# MCU.net
KiCad netlist of a schematic drawn in Altium Designer
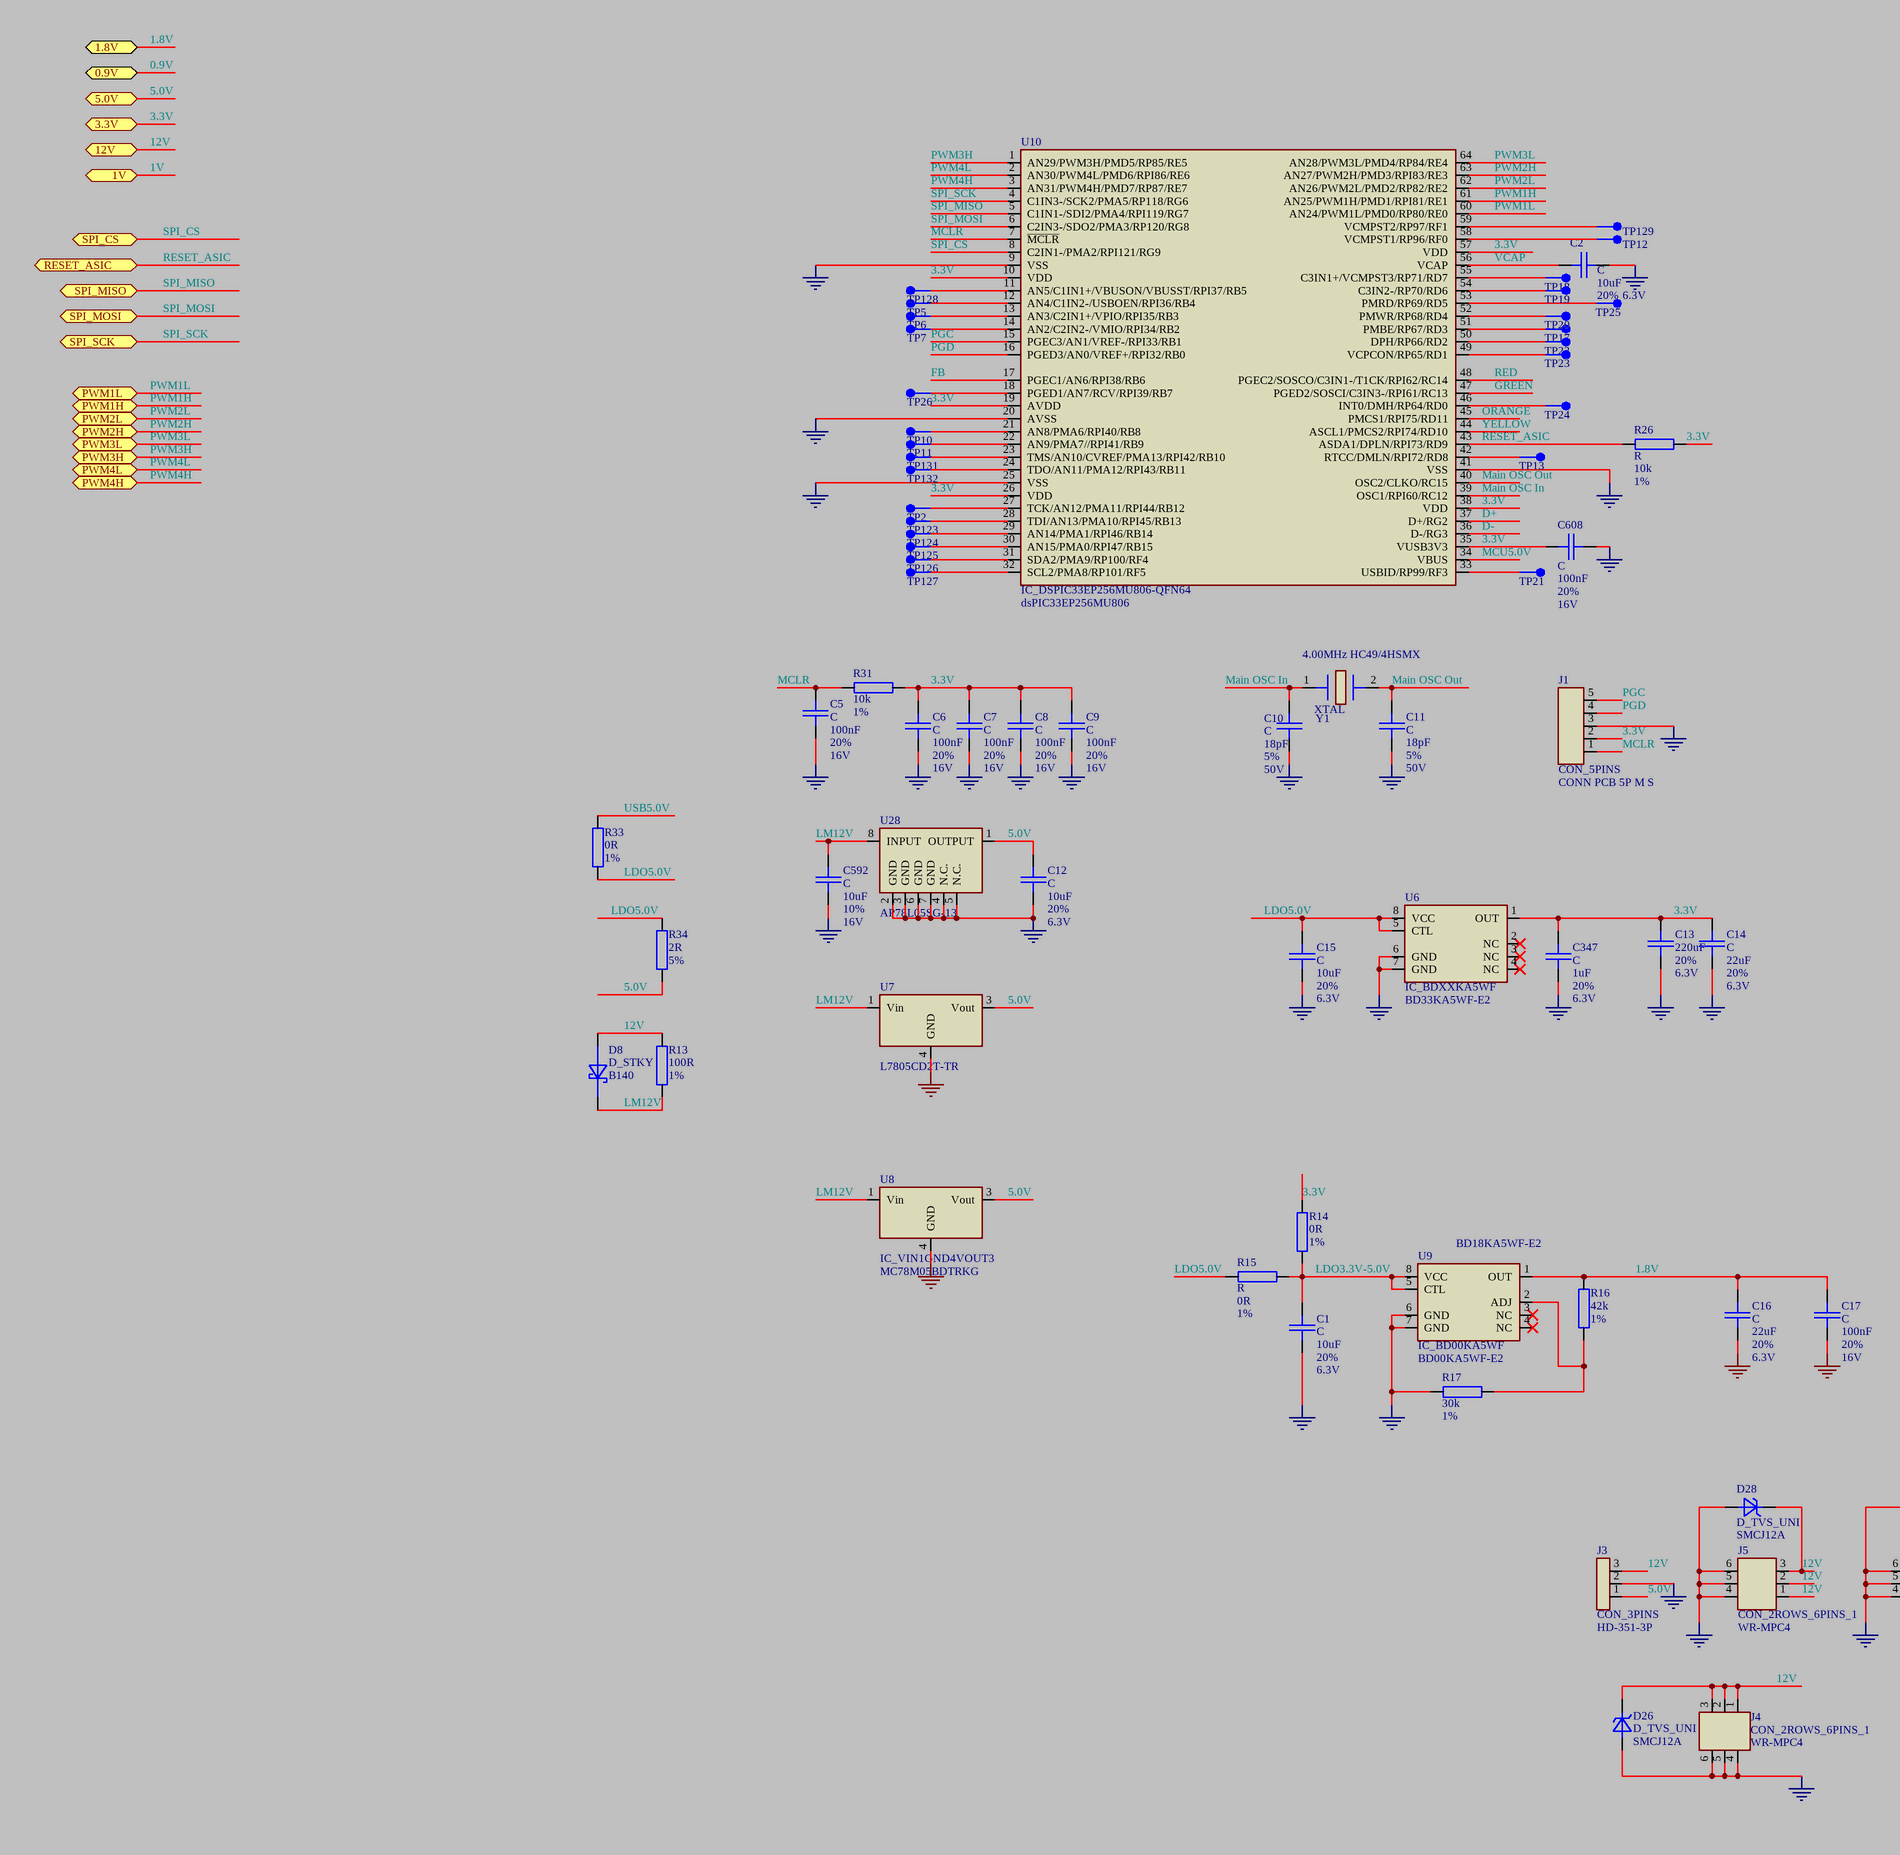
[diagram p0: MCU.SchDoc, left]
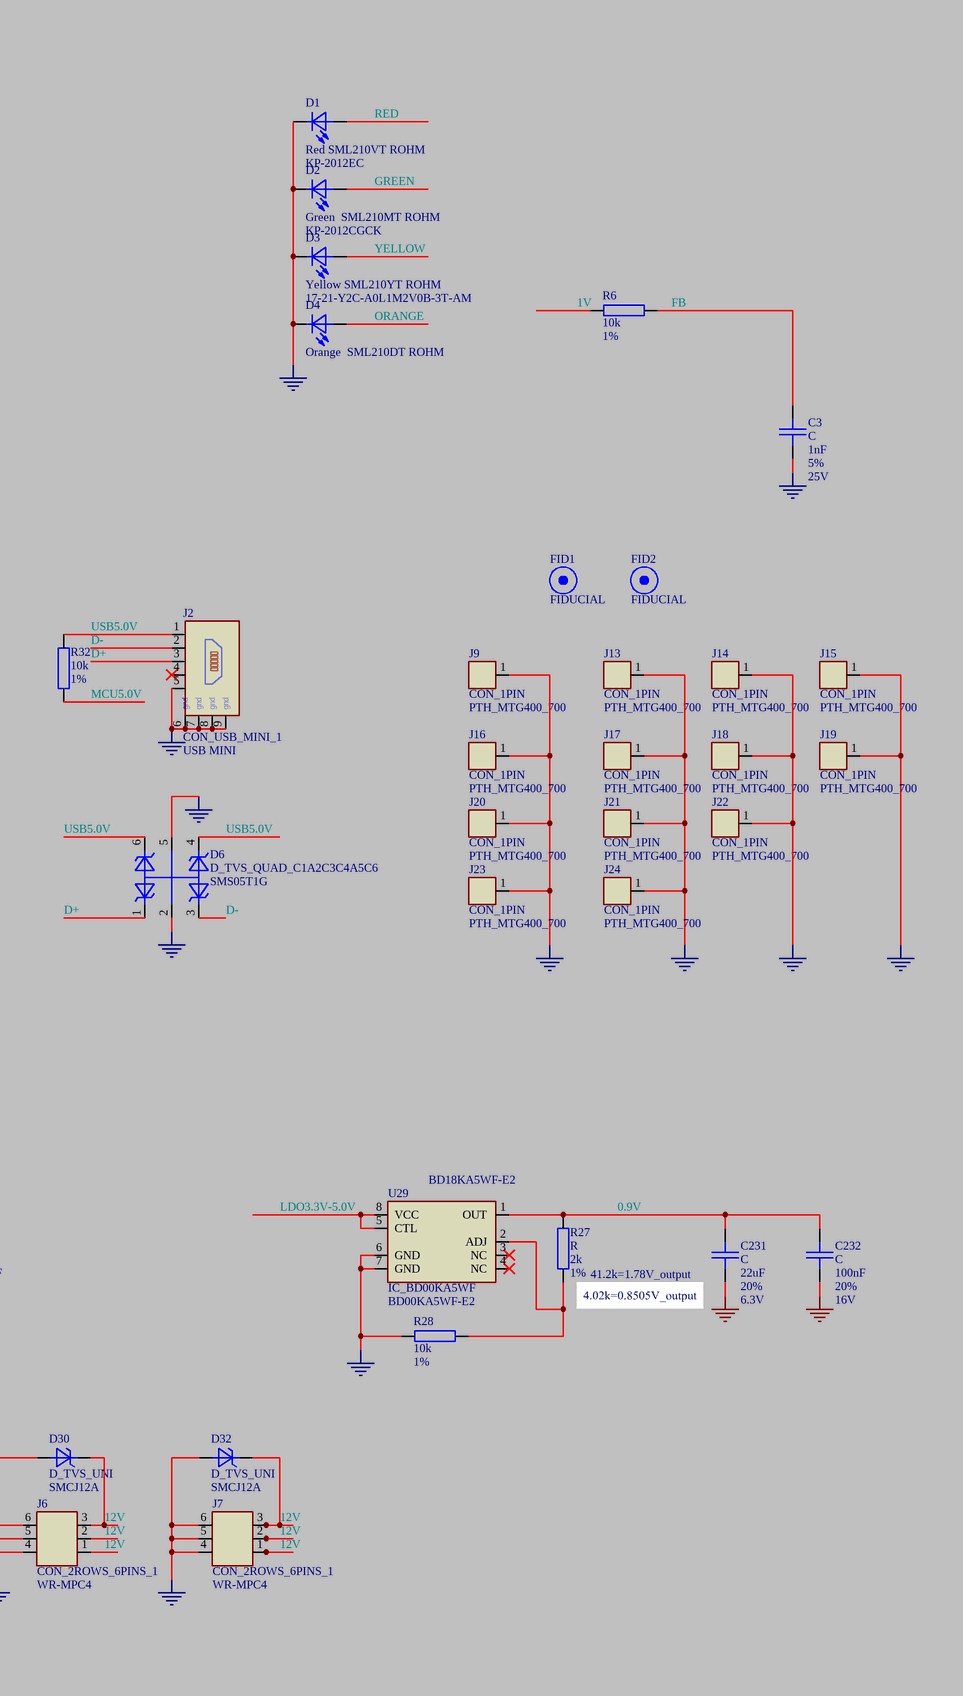
[diagram p1: MCU.SchDoc, right]

(export (version "E")
  (design (tool "Eeschema 10.0.6"))
  (components
    (comp (ref "C1")
      (value "C")
      (footprint "SMD_0603_CAPC1608X95N")
      (fields
        (field (name "DB_PART_NUMBER") "CAP000043646")
        (field (name "DB_VALUE") "10uF")
        (field (name "DB_TOLERANCE") "20%")
        (field (name "DB_VOLTAGE") "6.3V")
        (field (name "DB_MANUFACTURER_PART") "KEMET    C0603C106M9PAC")
        (field (name "DB_APPROVED_BY") "ISHIDDEN=T")
      )
      (libsource (lib "Database_Libs1") (part "C"))
    )
    (comp (ref "C2")
      (value "C")
      (footprint "SMD_0603_CAPC1608X95N")
      (fields
        (field (name "DB_PART_NUMBER") "CAP000043646")
        (field (name "DB_VALUE") "10uF")
        (field (name "DB_TOLERANCE") "20%")
        (field (name "DB_VOLTAGE") "6.3V")
        (field (name "DB_MANUFACTURER_PART") "KEMET    C0603C106M9PAC")
        (field (name "DB_APPROVED_BY") "ISHIDDEN=T")
      )
      (libsource (lib "Database_Libs1") (part "C"))
    )
    (comp (ref "C3")
      (value "C")
      (footprint "SMD_0603_CAPC1608X95N")
      (fields
        (field (name "DB_PART_NUMBER") "CAP000024113")
        (field (name "DB_VALUE") "1nF")
        (field (name "DB_TOLERANCE") "5%")
        (field (name "DB_VOLTAGE") "25V")
        (field (name "DB_MANUFACTURER_PART") "KEMET    C0603C102J3RAC")
        (field (name "DB_APPROVED_BY") "ISHIDDEN=T")
      )
      (libsource (lib "Database_Libs1") (part "C"))
    )
    (comp (ref "C5")
      (value "C")
      (footprint "SMD_0603_CAPC1608X95N")
      (fields
        (field (name "DB_PART_NUMBER") "CAP000027236")
        (field (name "DB_VALUE") "100nF")
        (field (name "DB_TOLERANCE") "20%")
        (field (name "DB_VOLTAGE") "16V")
        (field (name "DB_MANUFACTURER_PART") "KEMET    C0603C104M4RAC")
        (field (name "DB_APPROVED_BY") "ISHIDDEN=T")
      )
      (libsource (lib "Database_Libs1") (part "C"))
    )
    (comp (ref "C6")
      (value "C")
      (footprint "SMD_0603_CAPC1608X95N")
      (fields
        (field (name "DB_PART_NUMBER") "CAP000027236")
        (field (name "DB_VALUE") "100nF")
        (field (name "DB_TOLERANCE") "20%")
        (field (name "DB_VOLTAGE") "16V")
        (field (name "DB_MANUFACTURER_PART") "KEMET    C0603C104M4RAC")
        (field (name "DB_APPROVED_BY") "ISHIDDEN=T")
      )
      (libsource (lib "Database_Libs1") (part "C"))
    )
    (comp (ref "C7")
      (value "C")
      (footprint "SMD_0603_CAPC1608X95N")
      (fields
        (field (name "DB_PART_NUMBER") "CAP000027236")
        (field (name "DB_VALUE") "100nF")
        (field (name "DB_TOLERANCE") "20%")
        (field (name "DB_VOLTAGE") "16V")
        (field (name "DB_MANUFACTURER_PART") "KEMET    C0603C104M4RAC")
        (field (name "DB_APPROVED_BY") "ISHIDDEN=T")
      )
      (libsource (lib "Database_Libs1") (part "C"))
    )
    (comp (ref "C8")
      (value "C")
      (footprint "SMD_0603_CAPC1608X95N")
      (fields
        (field (name "DB_PART_NUMBER") "CAP000027236")
        (field (name "DB_VALUE") "100nF")
        (field (name "DB_TOLERANCE") "20%")
        (field (name "DB_VOLTAGE") "16V")
        (field (name "DB_MANUFACTURER_PART") "KEMET    C0603C104M4RAC")
        (field (name "DB_APPROVED_BY") "ISHIDDEN=T")
      )
      (libsource (lib "Database_Libs1") (part "C"))
    )
    (comp (ref "C9")
      (value "C")
      (footprint "SMD_0603_CAPC1608X95N")
      (fields
        (field (name "DB_PART_NUMBER") "CAP000027236")
        (field (name "DB_VALUE") "100nF")
        (field (name "DB_TOLERANCE") "20%")
        (field (name "DB_VOLTAGE") "16V")
        (field (name "DB_MANUFACTURER_PART") "KEMET    C0603C104M4RAC")
        (field (name "DB_APPROVED_BY") "ISHIDDEN=T")
      )
      (libsource (lib "Database_Libs1") (part "C"))
    )
    (comp (ref "C10")
      (value "C")
      (footprint "SMD_0603_CAPC1608X95N")
      (fields
        (field (name "DB_PART_NUMBER") "CAP000031922")
        (field (name "DB_VALUE") "18pF")
        (field (name "DB_TOLERANCE") "5%")
        (field (name "DB_VOLTAGE") "50V")
        (field (name "DB_MANUFACTURER_PART") "KEMET    C0603C180J5GAC")
        (field (name "DB_APPROVED_BY") "ISHIDDEN=T")
      )
      (libsource (lib "Database_Libs1") (part "C"))
    )
    (comp (ref "C11")
      (value "C")
      (footprint "SMD_0603_CAPC1608X95N")
      (fields
        (field (name "DB_PART_NUMBER") "CAP000031922")
        (field (name "DB_VALUE") "18pF")
        (field (name "DB_TOLERANCE") "5%")
        (field (name "DB_VOLTAGE") "50V")
        (field (name "DB_MANUFACTURER_PART") "KEMET    C0603C180J5GAC")
        (field (name "DB_APPROVED_BY") "ISHIDDEN=T")
      )
      (libsource (lib "Database_Libs1") (part "C"))
    )
    (comp (ref "C12")
      (value "C")
      (footprint "SMD_0603_CAPC1608X95N")
      (fields
        (field (name "DB_PART_NUMBER") "CAP000043646")
        (field (name "DB_VALUE") "10uF")
        (field (name "DB_TOLERANCE") "20%")
        (field (name "DB_VOLTAGE") "6.3V")
        (field (name "DB_MANUFACTURER_PART") "KEMET    C0603C106M9PAC")
        (field (name "DB_APPROVED_BY") "ISHIDDEN=T")
      )
      (libsource (lib "Database_Libs1") (part "C"))
    )
    (comp (ref "C13")
      (value "C")
      (footprint "SMD_1210_CAPC3225X279N")
      (fields
        (field (name "DB_PART_NUMBER") "CAP000047355")
        (field (name "DB_VALUE") "220uF")
        (field (name "DB_TOLERANCE") "20%")
        (field (name "DB_VOLTAGE") "6.3V")
        (field (name "DB_MANUFACTURER_PART") "SAMSUNG    CL32A227MQVNNNE")
        (field (name "DB_APPROVED_BY") "VSN")
      )
      (libsource (lib "Database_Libs1") (part "C"))
    )
    (comp (ref "C14")
      (value "C")
      (footprint "SMD_0805_CAPC2012X145N")
      (fields
        (field (name "DB_PART_NUMBER") "CAP000043686")
        (field (name "DB_VALUE") "22uF")
        (field (name "DB_TOLERANCE") "20%")
        (field (name "DB_VOLTAGE") "6.3V")
        (field (name "DB_MANUFACTURER_PART") "KEMET    C0805C226M9PAC")
        (field (name "DB_APPROVED_BY") "ISHIDDEN=T")
      )
      (libsource (lib "Database_Libs1") (part "C"))
    )
    (comp (ref "C15")
      (value "C")
      (footprint "SMD_0603_CAPC1608X95N")
      (fields
        (field (name "DB_PART_NUMBER") "CAP000043646")
        (field (name "DB_VALUE") "10uF")
        (field (name "DB_TOLERANCE") "20%")
        (field (name "DB_VOLTAGE") "6.3V")
        (field (name "DB_MANUFACTURER_PART") "KEMET    C0603C106M9PAC")
        (field (name "DB_APPROVED_BY") "ISHIDDEN=T")
      )
      (libsource (lib "Database_Libs1") (part "C"))
    )
    (comp (ref "C16")
      (value "C")
      (footprint "SMD_0805_CAPC2012X145N")
      (fields
        (field (name "DB_PART_NUMBER") "CAP000043686")
        (field (name "DB_VALUE") "22uF")
        (field (name "DB_TOLERANCE") "20%")
        (field (name "DB_VOLTAGE") "6.3V")
        (field (name "DB_MANUFACTURER_PART") "KEMET    C0805C226M9PAC")
        (field (name "DB_APPROVED_BY") "ISHIDDEN=T")
      )
      (libsource (lib "Database_Libs1") (part "C"))
    )
    (comp (ref "C17")
      (value "C")
      (footprint "SMD_0603_CAPC1608X95N")
      (fields
        (field (name "DB_PART_NUMBER") "CAP000027236")
        (field (name "DB_VALUE") "100nF")
        (field (name "DB_TOLERANCE") "20%")
        (field (name "DB_VOLTAGE") "16V")
        (field (name "DB_MANUFACTURER_PART") "KEMET    C0603C104M4RAC")
        (field (name "DB_APPROVED_BY") "ISHIDDEN=T")
      )
      (libsource (lib "Database_Libs1") (part "C"))
    )
    (comp (ref "C231")
      (value "C")
      (footprint "SMD_0805_CAPC2012X145N")
      (fields
        (field (name "DB_PART_NUMBER") "CAP000043686")
        (field (name "DB_VALUE") "22uF")
        (field (name "DB_TOLERANCE") "20%")
        (field (name "DB_VOLTAGE") "6.3V")
        (field (name "DB_MANUFACTURER_PART") "KEMET    C0805C226M9PAC")
        (field (name "DB_APPROVED_BY") "ISHIDDEN=T")
      )
      (libsource (lib "Database_Libs1") (part "C"))
    )
    (comp (ref "C232")
      (value "C")
      (footprint "SMD_0603_CAPC1608X95N")
      (fields
        (field (name "DB_PART_NUMBER") "CAP000027236")
        (field (name "DB_VALUE") "100nF")
        (field (name "DB_TOLERANCE") "20%")
        (field (name "DB_VOLTAGE") "16V")
        (field (name "DB_MANUFACTURER_PART") "KEMET    C0603C104M4RAC")
        (field (name "DB_APPROVED_BY") "ISHIDDEN=T")
      )
      (libsource (lib "Database_Libs1") (part "C"))
    )
    (comp (ref "C347")
      (value "C")
      (footprint "SMD_0603_CAPC1608X95N")
      (fields
        (field (name "DB_PART_NUMBER") "CAP000043344")
        (field (name "DB_VALUE") "1uF")
        (field (name "DB_TOLERANCE") "20%")
        (field (name "DB_VOLTAGE") "6.3V")
        (field (name "DB_MANUFACTURER_PART") "KEMET    C0603C105M9PAC")
        (field (name "DB_APPROVED_BY") "ISHIDDEN=T")
      )
      (libsource (lib "Database_Libs1") (part "C"))
    )
    (comp (ref "C592")
      (value "C")
      (footprint "SMD_0805_CAPC2012X145N")
      (fields
        (field (name "DB_PART_NUMBER") "CAP000043636")
        (field (name "DB_VALUE") "10uF")
        (field (name "DB_TOLERANCE") "10%")
        (field (name "DB_VOLTAGE") "16V")
        (field (name "DB_MANUFACTURER_PART") "KEMET    C0805C106K4PAC")
        (field (name "DB_APPROVED_BY") "ISHIDDEN=T")
      )
      (libsource (lib "Database_Libs1") (part "C"))
    )
    (comp (ref "C608")
      (value "C")
      (footprint "SMD_0603_CAPC1608X95N")
      (fields
        (field (name "DB_PART_NUMBER") "CAP000027236")
        (field (name "DB_VALUE") "100nF")
        (field (name "DB_TOLERANCE") "20%")
        (field (name "DB_VOLTAGE") "16V")
        (field (name "DB_MANUFACTURER_PART") "KEMET    C0603C104M4RAC")
        (field (name "DB_APPROVED_BY") "ISHIDDEN=T")
      )
      (libsource (lib "Database_Libs1") (part "C"))
    )
    (comp (ref "D1")
      (value "Red SML210VT ROHM")
      (footprint "SMD_0805_LED2012X100N")
      (fields
        (field (name "DB_PART_NUMBER") "OPT000000095")
        (field (name "DB_MANUFACTURER_PART") "KINGBRIGHT       KP-2012EC")
        (field (name "DB_VALUE") "KP-2012EC")
        (field (name "DB_APPROVED_BY") "VSN")
      )
      (libsource (lib "Database_Libs1") (part "LED"))
    )
    (comp (ref "D2")
      (value "Green  SML210MT ROHM")
      (footprint "SMD_0805_LED2012X100N")
      (fields
        (field (name "DB_PART_NUMBER") "OPT000000096")
        (field (name "DB_MANUFACTURER_PART") "KINGBRIGHT       KP-2012CGCK")
        (field (name "DB_VALUE") "KP-2012CGCK")
        (field (name "DB_APPROVED_BY") "VSN")
      )
      (libsource (lib "Database_Libs1") (part "LED"))
    )
    (comp (ref "D3")
      (value "Yellow SML210YT ROHM")
      (footprint "SMD_0805_LED2012X100N")
      (fields
        (field (name "DB_PART_NUMBER") "OPT000000092")
        (field (name "DB_MANUFACTURER_PART") "EVERLIGHT       17-21-Y2C-A0L1M2V0B-3T-AM")
        (field (name "DB_VALUE") "17-21-Y2C-A0L1M2V0B-3T-AM")
        (field (name "DB_APPROVED_BY") "VSN")
      )
      (libsource (lib "Database_Libs1") (part "LED"))
    )
    (comp (ref "D4")
      (value "Orange  SML210DT ROHM")
      (footprint "SMD_0805_LED2012X100N")
      (fields
        (field (name "DB_PART_NUMBER") "OPT000000096")
        (field (name "DB_MANUFACTURER_PART") "KINGBRIGHT       KP-2012CGCK")
        (field (name "DB_APPROVED_BY") "VSN")
      )
      (libsource (lib "altium-import") (part "root_0_LED_Orange_"))
    )
    (comp (ref "D6")
      (value "D_TVS_QUAD_C1A2C3C4A5C6")
      (footprint "SMD_SOT457_SOT95P275X110-6N")
      (fields
        (field (name "DB_PART_NUMBER") "DDE000002846")
        (field (name "DB_VALUE") "SMS05T1G")
        (field (name "DB_MANUFACTURER_PART") "ON SEMICONDUCTOR        SMS05T1G")
        (field (name "DB_APPROVED_BY") "VSN")
      )
      (libsource (lib "Database_Libs1") (part "D_TVS_QUAD_C1A2C3C4A5C6"))
    )
    (comp (ref "D8")
      (value "D_STKY")
      (footprint "SMD_DO214AC_SMA")
      (fields
        (field (name "DB_PART_NUMBER") "DDE000000580")
        (field (name "DB_VALUE") "B140")
        (field (name "DB_MANUFACTURER_PART") "Diodes        B140")
        (field (name "DB_APPROVED_BY") "ISHIDDEN=T")
      )
      (libsource (lib "Database_Libs1") (part "D_STKY"))
    )
    (comp (ref "D26")
      (value "D_TVS_UNI")
      (footprint "SMD_DO214AC_SMC")
      (fields
        (field (name "DB_PART_NUMBER") "DDE000001725")
        (field (name "DB_VALUE") "SMCJ12A")
        (field (name "DB_MANUFACTURER_PART") "Diodes        SMCJ12A")
        (field (name "DB_APPROVED_BY") "ISHIDDEN=T")
      )
      (libsource (lib "Database_Libs1") (part "D_TVS_UNI"))
    )
    (comp (ref "D28")
      (value "D_TVS_UNI")
      (footprint "SMD_DO214AC_SMC")
      (fields
        (field (name "DB_PART_NUMBER") "DDE000001725")
        (field (name "DB_VALUE") "SMCJ12A")
        (field (name "DB_MANUFACTURER_PART") "Diodes        SMCJ12A")
        (field (name "DB_APPROVED_BY") "ISHIDDEN=T")
      )
      (libsource (lib "Database_Libs1") (part "D_TVS_UNI"))
    )
    (comp (ref "D30")
      (value "D_TVS_UNI")
      (footprint "SMD_DO214AC_SMC")
      (fields
        (field (name "DB_PART_NUMBER") "DDE000001725")
        (field (name "DB_VALUE") "SMCJ12A")
        (field (name "DB_MANUFACTURER_PART") "Diodes        SMCJ12A")
        (field (name "DB_APPROVED_BY") "ISHIDDEN=T")
      )
      (libsource (lib "Database_Libs1") (part "D_TVS_UNI"))
    )
    (comp (ref "D32")
      (value "D_TVS_UNI")
      (footprint "SMD_DO214AC_SMC")
      (fields
        (field (name "DB_PART_NUMBER") "DDE000001725")
        (field (name "DB_VALUE") "SMCJ12A")
        (field (name "DB_MANUFACTURER_PART") "Diodes        SMCJ12A")
        (field (name "DB_APPROVED_BY") "ISHIDDEN=T")
      )
      (libsource (lib "Database_Libs1") (part "D_TVS_UNI"))
    )
    (comp (ref "FID1")
      (value "FIDUCIAL")
      (footprint "FID100X200")
      (fields
        (field (name "DB_PART_NUMBER") "FID000000001")
        (field (name "DB_MANUFACTURER_PART") "ISHIDDEN=T")
        (field (name "DB_APPROVED_BY") "ISHIDDEN=T")
      )
      (libsource (lib "Database_Libs1") (part "FIDUCIAL"))
    )
    (comp (ref "FID2")
      (value "FIDUCIAL")
      (footprint "FID100X200")
      (fields
        (field (name "DB_PART_NUMBER") "FID000000001")
        (field (name "DB_MANUFACTURER_PART") "ISHIDDEN=T")
        (field (name "DB_APPROVED_BY") "ISHIDDEN=T")
      )
      (libsource (lib "Database_Libs1") (part "FIDUCIAL"))
    )
    (comp (ref "J1")
      (value "CON_5PINS")
      (footprint "PTH_HDRV05W64P254_1X05")
      (fields
        (field (name "DB_PART_NUMBER") "CON000000006")
        (field (name "DB_VALUE") "CONN PCB 5P M S")
        (field (name "DB_MANUFACTURER_PART") "W+P        143-12-005-00")
        (field (name "DB_APPROVED_BY") "VSN")
      )
      (libsource (lib "Database_Libs1") (part "CON_5PINS"))
    )
    (comp (ref "J2")
      (value "CON_USB_MINI_1")
      (footprint "SMD_CON-CVILUX-CU04-SCM15B0")
      (fields
        (field (name "DB_PART_NUMBER") "CON000000048")
        (field (name "DB_VALUE") "USB MINI")
        (field (name "DB_MANUFACTURER_PART") "CVILUX       CU04-SCM15B0-R0-LF")
        (field (name "DB_APPROVED_BY") "VSN")
      )
      (libsource (lib "Database_Libs1") (part "CON_USB_MINI_1"))
    )
    (comp (ref "J3")
      (value "CON_3PINS")
      (footprint "PTH_CON_HD-351-3P")
      (fields
        (field (name "DB_PART_NUMBER") "CON000000272")
        (field (name "DB_VALUE") "HD-351-3P")
        (field (name "DB_MANUFACTURER_PART") "HOW DER      HD-351-3P")
        (field (name "DB_APPROVED_BY") "VSN")
      )
      (libsource (lib "Database_Libs1") (part "CON_3PINS"))
    )
    (comp (ref "J4")
      (value "CON_2ROWS_6PINS_1")
      (footprint "PTH_CON_WR-MRC4-6P")
      (fields
        (field (name "DB_PART_NUMBER") "CON000000271")
        (field (name "DB_VALUE") "WR-MPC4")
        (field (name "DB_MANUFACTURER_PART") "WE         649 006 295 22")
        (field (name "DB_APPROVED_BY") "VSN")
      )
      (libsource (lib "") (part "CON_2ROWS_6PINS_1_1"))
    )
    (comp (ref "J5")
      (value "CON_2ROWS_6PINS_1")
      (footprint "PTH_CON_WR-MRC4-6P")
      (fields
        (field (name "DB_PART_NUMBER") "CON000000271")
        (field (name "DB_VALUE") "WR-MPC4")
        (field (name "DB_MANUFACTURER_PART") "WE         649 006 295 22")
        (field (name "DB_APPROVED_BY") "VSN")
      )
      (libsource (lib "Database_Libs1") (part "CON_2ROWS_6PINS_1"))
    )
    (comp (ref "J6")
      (value "CON_2ROWS_6PINS_1")
      (footprint "PTH_CON_WR-MRC4-6P")
      (fields
        (field (name "DB_PART_NUMBER") "CON000000271")
        (field (name "DB_VALUE") "WR-MPC4")
        (field (name "DB_MANUFACTURER_PART") "WE         649 006 295 22")
        (field (name "DB_APPROVED_BY") "VSN")
      )
      (libsource (lib "Database_Libs1") (part "CON_2ROWS_6PINS_1"))
    )
    (comp (ref "J7")
      (value "CON_2ROWS_6PINS_1")
      (footprint "PTH_CON_WR-MRC4-6P")
      (fields
        (field (name "DB_PART_NUMBER") "CON000000271")
        (field (name "DB_VALUE") "WR-MPC4")
        (field (name "DB_MANUFACTURER_PART") "WE         649 006 295 22")
        (field (name "DB_APPROVED_BY") "VSN")
      )
      (libsource (lib "Database_Libs1") (part "CON_2ROWS_6PINS_1"))
    )
    (comp (ref "J9")
      (value "CON_1PIN")
      (footprint "PTH_MTG400_700")
      (fields
        (field (name "DB_PART_NUMBER") "MTH000000030")
        (field (name "DB_VALUE") "PTH_MTG400_700")
        (field (name "DB_APPROVED_BY") "VSN")
      )
      (libsource (lib "Database_Libs1") (part "CON_1PIN"))
    )
    (comp (ref "J13")
      (value "CON_1PIN")
      (footprint "PTH_MTG400_700")
      (fields
        (field (name "DB_PART_NUMBER") "MTH000000030")
        (field (name "DB_VALUE") "PTH_MTG400_700")
        (field (name "DB_APPROVED_BY") "VSN")
      )
      (libsource (lib "Database_Libs1") (part "CON_1PIN"))
    )
    (comp (ref "J14")
      (value "CON_1PIN")
      (footprint "PTH_MTG400_700")
      (fields
        (field (name "DB_PART_NUMBER") "MTH000000030")
        (field (name "DB_VALUE") "PTH_MTG400_700")
        (field (name "DB_APPROVED_BY") "VSN")
      )
      (libsource (lib "Database_Libs1") (part "CON_1PIN"))
    )
    (comp (ref "J15")
      (value "CON_1PIN")
      (footprint "PTH_MTG400_700")
      (fields
        (field (name "DB_PART_NUMBER") "MTH000000030")
        (field (name "DB_VALUE") "PTH_MTG400_700")
        (field (name "DB_APPROVED_BY") "VSN")
      )
      (libsource (lib "Database_Libs1") (part "CON_1PIN"))
    )
    (comp (ref "J16")
      (value "CON_1PIN")
      (footprint "PTH_MTG400_700")
      (fields
        (field (name "DB_PART_NUMBER") "MTH000000030")
        (field (name "DB_VALUE") "PTH_MTG400_700")
        (field (name "DB_APPROVED_BY") "VSN")
      )
      (libsource (lib "Database_Libs1") (part "CON_1PIN"))
    )
    (comp (ref "J17")
      (value "CON_1PIN")
      (footprint "PTH_MTG400_700")
      (fields
        (field (name "DB_PART_NUMBER") "MTH000000030")
        (field (name "DB_VALUE") "PTH_MTG400_700")
        (field (name "DB_APPROVED_BY") "VSN")
      )
      (libsource (lib "Database_Libs1") (part "CON_1PIN"))
    )
    (comp (ref "J18")
      (value "CON_1PIN")
      (footprint "PTH_MTG400_700")
      (fields
        (field (name "DB_PART_NUMBER") "MTH000000030")
        (field (name "DB_VALUE") "PTH_MTG400_700")
        (field (name "DB_APPROVED_BY") "VSN")
      )
      (libsource (lib "Database_Libs1") (part "CON_1PIN"))
    )
    (comp (ref "J19")
      (value "CON_1PIN")
      (footprint "PTH_MTG400_700")
      (fields
        (field (name "DB_PART_NUMBER") "MTH000000030")
        (field (name "DB_VALUE") "PTH_MTG400_700")
        (field (name "DB_APPROVED_BY") "VSN")
      )
      (libsource (lib "Database_Libs1") (part "CON_1PIN"))
    )
    (comp (ref "J20")
      (value "CON_1PIN")
      (footprint "PTH_MTG400_700")
      (fields
        (field (name "DB_PART_NUMBER") "MTH000000030")
        (field (name "DB_VALUE") "PTH_MTG400_700")
        (field (name "DB_APPROVED_BY") "VSN")
      )
      (libsource (lib "Database_Libs1") (part "CON_1PIN"))
    )
    (comp (ref "J21")
      (value "CON_1PIN")
      (footprint "PTH_MTG400_700")
      (fields
        (field (name "DB_PART_NUMBER") "MTH000000030")
        (field (name "DB_VALUE") "PTH_MTG400_700")
        (field (name "DB_APPROVED_BY") "VSN")
      )
      (libsource (lib "Database_Libs1") (part "CON_1PIN"))
    )
    (comp (ref "J22")
      (value "CON_1PIN")
      (footprint "PTH_MTG400_700")
      (fields
        (field (name "DB_PART_NUMBER") "MTH000000030")
        (field (name "DB_VALUE") "PTH_MTG400_700")
        (field (name "DB_APPROVED_BY") "VSN")
      )
      (libsource (lib "Database_Libs1") (part "CON_1PIN"))
    )
    (comp (ref "J23")
      (value "CON_1PIN")
      (footprint "PTH_MTG400_700")
      (fields
        (field (name "DB_PART_NUMBER") "MTH000000030")
        (field (name "DB_VALUE") "PTH_MTG400_700")
        (field (name "DB_APPROVED_BY") "VSN")
      )
      (libsource (lib "Database_Libs1") (part "CON_1PIN"))
    )
    (comp (ref "J24")
      (value "CON_1PIN")
      (footprint "PTH_MTG400_700")
      (fields
        (field (name "DB_PART_NUMBER") "MTH000000030")
        (field (name "DB_VALUE") "PTH_MTG400_700")
        (field (name "DB_APPROVED_BY") "VSN")
      )
      (libsource (lib "Database_Libs1") (part "CON_1PIN"))
    )
    (comp (ref "R6")
      (value "R")
      (footprint "SMD_0603_RESC1608X55N")
      (fields
        (field (name "DB_PART_NUMBER") "RES000008663")
        (field (name "DB_VALUE") "10k")
        (field (name "DB_TOLERANCE") "1%")
        (field (name "DB_MANUFACTURER_PART") "YAGEO    RC0603FR-0710KL")
        (field (name "DB_APPROVED_BY") "VSN")
      )
      (libsource (lib "Database_Libs1") (part "R"))
    )
    (comp (ref "R13")
      (value "R")
      (footprint "SMD_1206_RESC3216X65N")
      (fields
        (field (name "DB_PART_NUMBER") "RES000006922")
        (field (name "DB_VALUE") "100R")
        (field (name "DB_TOLERANCE") "1%")
        (field (name "DB_MANUFACTURER_PART") "YAGEO    RC1206FR-07100R")
        (field (name "DB_APPROVED_BY") "ISHIDDEN=T")
      )
      (libsource (lib "Database_Libs1") (part "R"))
    )
    (comp (ref "R14")
      (value "R")
      (footprint "SMD_1206_RESC3216X65N")
      (fields
        (field (name "DB_PART_NUMBER") "RES000008756")
        (field (name "DB_VALUE") "0R")
        (field (name "DB_TOLERANCE") "1%")
        (field (name "DB_MANUFACTURER_PART") "YAGEO    AC1206FR-070RL")
        (field (name "DB_APPROVED_BY") "VSN")
      )
      (libsource (lib "Database_Libs1") (part "R"))
    )
    (comp (ref "R15")
      (value "R")
      (footprint "SMD_1206_RESC3216X65N")
      (fields
        (field (name "DB_PART_NUMBER") "RES000008756")
        (field (name "DB_VALUE") "0R")
        (field (name "DB_TOLERANCE") "1%")
        (field (name "DB_MANUFACTURER_PART") "YAGEO    AC1206FR-070RL")
        (field (name "DB_APPROVED_BY") "VSN")
      )
      (libsource (lib "Database_Libs1") (part "R"))
    )
    (comp (ref "R16")
      (value "R_42k")
      (footprint "SMD_0603_RESC1608X55N")
      (fields
        (field (name "DB_PART_NUMBER") "RES000001590")
        (field (name "DB_VALUE") "42k")
        (field (name "DB_TOLERANCE") "1%")
        (field (name "DB_MANUFACTURER_PART") "YAGEO    RC0603FR-0741K2")
        (field (name "DB_APPROVED_BY") "ISHIDDEN=T")
      )
      (libsource (lib "Schlib1") (part "R_42k"))
    )
    (comp (ref "R17")
      (value "R")
      (footprint "SMD_0603_RESC1608X55N")
      (fields
        (field (name "DB_PART_NUMBER") "RES000006287")
        (field (name "DB_VALUE") "30k")
        (field (name "DB_TOLERANCE") "1%")
        (field (name "DB_MANUFACTURER_PART") "YAGEO    RC0603FR-0730K")
        (field (name "DB_APPROVED_BY") "ISHIDDEN=T")
      )
      (libsource (lib "Database_Libs1") (part "R"))
    )
    (comp (ref "R26")
      (value "R")
      (footprint "SMD_0603_RESC1608X55N")
      (fields
        (field (name "DB_PART_NUMBER") "RES000008663")
        (field (name "DB_VALUE") "10k")
        (field (name "DB_TOLERANCE") "1%")
        (field (name "DB_MANUFACTURER_PART") "YAGEO    RC0603FR-0710KL")
        (field (name "DB_APPROVED_BY") "VSN")
      )
      (libsource (lib "Database_Libs1") (part "R"))
    )
    (comp (ref "R27")
      (value "R")
      (footprint "SMD_0603_RESC1608X55N")
      (fields
        (field (name "DB_PART_NUMBER") "RES000008586")
        (field (name "DB_VALUE") "2k")
        (field (name "DB_TOLERANCE") "1%")
        (field (name "DB_MANUFACTURER_PART") "YAGEO       AC0603FR-072KL")
        (field (name "DB_APPROVED_BY") "VSN")
      )
      (libsource (lib "Database_Libs1") (part "R"))
    )
    (comp (ref "R28")
      (value "R")
      (footprint "SMD_0603_RESC1608X55N")
      (fields
        (field (name "DB_PART_NUMBER") "RES000008663")
        (field (name "DB_VALUE") "10k")
        (field (name "DB_TOLERANCE") "1%")
        (field (name "DB_MANUFACTURER_PART") "YAGEO    RC0603FR-0710KL")
        (field (name "DB_APPROVED_BY") "VSN")
      )
      (libsource (lib "Database_Libs1") (part "R"))
    )
    (comp (ref "R31")
      (value "R")
      (footprint "SMD_0603_RESC1608X55N")
      (fields
        (field (name "DB_PART_NUMBER") "RES000008663")
        (field (name "DB_VALUE") "10k")
        (field (name "DB_TOLERANCE") "1%")
        (field (name "DB_MANUFACTURER_PART") "YAGEO    RC0603FR-0710KL")
        (field (name "DB_APPROVED_BY") "VSN")
      )
      (libsource (lib "Database_Libs1") (part "R"))
    )
    (comp (ref "R32")
      (value "R")
      (footprint "SMD_0603_RESC1608X55N")
      (fields
        (field (name "DB_PART_NUMBER") "RES000008663")
        (field (name "DB_VALUE") "10k")
        (field (name "DB_TOLERANCE") "1%")
        (field (name "DB_MANUFACTURER_PART") "YAGEO    RC0603FR-0710KL")
        (field (name "DB_APPROVED_BY") "VSN")
      )
      (libsource (lib "Database_Libs1") (part "R"))
    )
    (comp (ref "R33")
      (value "R")
      (footprint "SMD_0603_RESC1608X55N")
      (fields
        (field (name "DB_PART_NUMBER") "RES000008926")
        (field (name "DB_VALUE") "0R")
        (field (name "DB_TOLERANCE") "1%")
        (field (name "DB_MANUFACTURER_PART") "YAGEO    AC0603FR-070RL")
        (field (name "DB_APPROVED_BY") "VSN")
      )
      (libsource (lib "Database_Libs1") (part "R"))
    )
    (comp (ref "R34")
      (value "R")
      (footprint "SMD_1206_RESC3216X65N")
      (fields
        (field (name "DB_PART_NUMBER") "RES000007051")
        (field (name "DB_VALUE") "2R")
        (field (name "DB_TOLERANCE") "5%")
        (field (name "DB_MANUFACTURER_PART") "YAGEO    RC1206JR-072R")
        (field (name "DB_APPROVED_BY") "ISHIDDEN=T")
      )
      (libsource (lib "Database_Libs1") (part "R"))
    )
    (comp (ref "TP2")
      (value "TEST_POINT_1")
      (footprint "SMD_TP_100-254")
      (fields
        (field (name "DB_PART_NUMBER") "TPO000000001")
        (field (name "DB_MANUFACTURER_PART") "ISHIDDEN=T")
        (field (name "DB_APPROVED_BY") "ISHIDDEN=T")
      )
      (libsource (lib "Database_Libs1") (part "TEST_POINT_1"))
    )
    (comp (ref "TP5")
      (value "TEST_POINT_1")
      (footprint "SMD_TP_100-254")
      (fields
        (field (name "DB_PART_NUMBER") "TPO000000001")
        (field (name "DB_MANUFACTURER_PART") "ISHIDDEN=T")
        (field (name "DB_APPROVED_BY") "ISHIDDEN=T")
      )
      (libsource (lib "Database_Libs1") (part "TEST_POINT_1"))
    )
    (comp (ref "TP6")
      (value "TEST_POINT_1")
      (footprint "SMD_TP_100-254")
      (fields
        (field (name "DB_PART_NUMBER") "TPO000000001")
        (field (name "DB_MANUFACTURER_PART") "ISHIDDEN=T")
        (field (name "DB_APPROVED_BY") "ISHIDDEN=T")
      )
      (libsource (lib "Database_Libs1") (part "TEST_POINT_1"))
    )
    (comp (ref "TP7")
      (value "TEST_POINT_1")
      (footprint "SMD_TP_100-254")
      (fields
        (field (name "DB_PART_NUMBER") "TPO000000001")
        (field (name "DB_MANUFACTURER_PART") "ISHIDDEN=T")
        (field (name "DB_APPROVED_BY") "ISHIDDEN=T")
      )
      (libsource (lib "Database_Libs1") (part "TEST_POINT_1"))
    )
    (comp (ref "TP10")
      (value "TEST_POINT_1")
      (footprint "SMD_TP_100-254")
      (fields
        (field (name "DB_PART_NUMBER") "TPO000000001")
        (field (name "DB_MANUFACTURER_PART") "ISHIDDEN=T")
        (field (name "DB_APPROVED_BY") "ISHIDDEN=T")
      )
      (libsource (lib "Database_Libs1") (part "TEST_POINT_1"))
    )
    (comp (ref "TP11")
      (value "TEST_POINT_1")
      (footprint "SMD_TP_100-254")
      (fields
        (field (name "DB_PART_NUMBER") "TPO000000001")
        (field (name "DB_MANUFACTURER_PART") "ISHIDDEN=T")
        (field (name "DB_APPROVED_BY") "ISHIDDEN=T")
      )
      (libsource (lib "Database_Libs1") (part "TEST_POINT_1"))
    )
    (comp (ref "TP12")
      (value "TEST_POINT_1")
      (footprint "SMD_TP_100-254")
      (fields
        (field (name "DB_PART_NUMBER") "TPO000000001")
        (field (name "DB_MANUFACTURER_PART") "ISHIDDEN=T")
        (field (name "DB_APPROVED_BY") "ISHIDDEN=T")
      )
      (libsource (lib "Database_Libs1") (part "TEST_POINT_1"))
    )
    (comp (ref "TP13")
      (value "TEST_POINT_1")
      (footprint "SMD_TP_100-254")
      (fields
        (field (name "DB_PART_NUMBER") "TPO000000001")
        (field (name "DB_MANUFACTURER_PART") "ISHIDDEN=T")
        (field (name "DB_APPROVED_BY") "ISHIDDEN=T")
      )
      (libsource (lib "Database_Libs1") (part "TEST_POINT_1"))
    )
    (comp (ref "TP17")
      (value "TEST_POINT_1")
      (footprint "SMD_TP_100-254")
      (fields
        (field (name "DB_PART_NUMBER") "TPO000000001")
        (field (name "DB_MANUFACTURER_PART") "ISHIDDEN=T")
        (field (name "DB_APPROVED_BY") "ISHIDDEN=T")
      )
      (libsource (lib "Database_Libs1") (part "TEST_POINT_1"))
    )
    (comp (ref "TP18")
      (value "TEST_POINT_1")
      (footprint "SMD_TP_100-254")
      (fields
        (field (name "DB_PART_NUMBER") "TPO000000001")
        (field (name "DB_MANUFACTURER_PART") "ISHIDDEN=T")
        (field (name "DB_APPROVED_BY") "ISHIDDEN=T")
      )
      (libsource (lib "Database_Libs1") (part "TEST_POINT_1"))
    )
    (comp (ref "TP19")
      (value "TEST_POINT_1")
      (footprint "SMD_TP_100-254")
      (fields
        (field (name "DB_PART_NUMBER") "TPO000000001")
        (field (name "DB_MANUFACTURER_PART") "ISHIDDEN=T")
        (field (name "DB_APPROVED_BY") "ISHIDDEN=T")
      )
      (libsource (lib "Database_Libs1") (part "TEST_POINT_1"))
    )
    (comp (ref "TP20")
      (value "TEST_POINT_1")
      (footprint "SMD_TP_100-254")
      (fields
        (field (name "DB_PART_NUMBER") "TPO000000001")
        (field (name "DB_MANUFACTURER_PART") "ISHIDDEN=T")
        (field (name "DB_APPROVED_BY") "ISHIDDEN=T")
      )
      (libsource (lib "Database_Libs1") (part "TEST_POINT_1"))
    )
    (comp (ref "TP21")
      (value "TEST_POINT_1")
      (footprint "SMD_TP_100-254")
      (fields
        (field (name "DB_PART_NUMBER") "TPO000000001")
        (field (name "DB_MANUFACTURER_PART") "ISHIDDEN=T")
        (field (name "DB_APPROVED_BY") "ISHIDDEN=T")
      )
      (libsource (lib "Database_Libs1") (part "TEST_POINT_1"))
    )
    (comp (ref "TP22")
      (value "TEST_POINT_1")
      (footprint "SMD_TP_100-254")
      (fields
        (field (name "DB_PART_NUMBER") "TPO000000001")
        (field (name "DB_MANUFACTURER_PART") "ISHIDDEN=T")
        (field (name "DB_APPROVED_BY") "ISHIDDEN=T")
      )
      (libsource (lib "Database_Libs1") (part "TEST_POINT_1"))
    )
    (comp (ref "TP23")
      (value "TEST_POINT_1")
      (footprint "SMD_TP_100-254")
      (fields
        (field (name "DB_PART_NUMBER") "TPO000000001")
        (field (name "DB_MANUFACTURER_PART") "ISHIDDEN=T")
        (field (name "DB_APPROVED_BY") "ISHIDDEN=T")
      )
      (libsource (lib "Database_Libs1") (part "TEST_POINT_1"))
    )
    (comp (ref "TP24")
      (value "TEST_POINT_1")
      (footprint "SMD_TP_100-254")
      (fields
        (field (name "DB_PART_NUMBER") "TPO000000001")
        (field (name "DB_MANUFACTURER_PART") "ISHIDDEN=T")
        (field (name "DB_APPROVED_BY") "ISHIDDEN=T")
      )
      (libsource (lib "Database_Libs1") (part "TEST_POINT_1"))
    )
    (comp (ref "TP25")
      (value "TEST_POINT_1")
      (footprint "SMD_TP_100-254")
      (fields
        (field (name "DB_PART_NUMBER") "TPO000000001")
        (field (name "DB_MANUFACTURER_PART") "ISHIDDEN=T")
        (field (name "DB_APPROVED_BY") "ISHIDDEN=T")
      )
      (libsource (lib "Database_Libs1") (part "TEST_POINT_1"))
    )
    (comp (ref "TP26")
      (value "TEST_POINT_1")
      (footprint "SMD_TP_100-254")
      (fields
        (field (name "DB_PART_NUMBER") "TPO000000001")
        (field (name "DB_MANUFACTURER_PART") "ISHIDDEN=T")
        (field (name "DB_APPROVED_BY") "ISHIDDEN=T")
      )
      (libsource (lib "Database_Libs1") (part "TEST_POINT_1"))
    )
    (comp (ref "TP123")
      (value "TEST_POINT_1")
      (footprint "SMD_TP_100-254")
      (fields
        (field (name "DB_PART_NUMBER") "TPO000000001")
        (field (name "DB_MANUFACTURER_PART") "ISHIDDEN=T")
        (field (name "DB_APPROVED_BY") "ISHIDDEN=T")
      )
      (libsource (lib "Database_Libs1") (part "TEST_POINT_1"))
    )
    (comp (ref "TP124")
      (value "TEST_POINT_1")
      (footprint "SMD_TP_100-254")
      (fields
        (field (name "DB_PART_NUMBER") "TPO000000001")
        (field (name "DB_MANUFACTURER_PART") "ISHIDDEN=T")
        (field (name "DB_APPROVED_BY") "ISHIDDEN=T")
      )
      (libsource (lib "Database_Libs1") (part "TEST_POINT_1"))
    )
    (comp (ref "TP125")
      (value "TEST_POINT_1")
      (footprint "SMD_TP_100-254")
      (fields
        (field (name "DB_PART_NUMBER") "TPO000000001")
        (field (name "DB_MANUFACTURER_PART") "ISHIDDEN=T")
        (field (name "DB_APPROVED_BY") "ISHIDDEN=T")
      )
      (libsource (lib "Database_Libs1") (part "TEST_POINT_1"))
    )
    (comp (ref "TP126")
      (value "TEST_POINT_1")
      (footprint "SMD_TP_100-254")
      (fields
        (field (name "DB_PART_NUMBER") "TPO000000001")
        (field (name "DB_MANUFACTURER_PART") "ISHIDDEN=T")
        (field (name "DB_APPROVED_BY") "ISHIDDEN=T")
      )
      (libsource (lib "Database_Libs1") (part "TEST_POINT_1"))
    )
    (comp (ref "TP127")
      (value "TEST_POINT_1")
      (footprint "SMD_TP_100-254")
      (fields
        (field (name "DB_PART_NUMBER") "TPO000000001")
        (field (name "DB_MANUFACTURER_PART") "ISHIDDEN=T")
        (field (name "DB_APPROVED_BY") "ISHIDDEN=T")
      )
      (libsource (lib "Database_Libs1") (part "TEST_POINT_1"))
    )
    (comp (ref "TP128")
      (value "TEST_POINT_1")
      (footprint "SMD_TP_100-254")
      (fields
        (field (name "DB_PART_NUMBER") "TPO000000001")
        (field (name "DB_MANUFACTURER_PART") "ISHIDDEN=T")
        (field (name "DB_APPROVED_BY") "ISHIDDEN=T")
      )
      (libsource (lib "Database_Libs1") (part "TEST_POINT_1"))
    )
    (comp (ref "TP129")
      (value "TEST_POINT_1")
      (footprint "SMD_TP_100-254")
      (fields
        (field (name "DB_PART_NUMBER") "TPO000000001")
        (field (name "DB_MANUFACTURER_PART") "ISHIDDEN=T")
        (field (name "DB_APPROVED_BY") "ISHIDDEN=T")
      )
      (libsource (lib "Database_Libs1") (part "TEST_POINT_1"))
    )
    (comp (ref "TP131")
      (value "TEST_POINT_1")
      (footprint "SMD_TP_100-254")
      (fields
        (field (name "DB_PART_NUMBER") "TPO000000001")
        (field (name "DB_MANUFACTURER_PART") "ISHIDDEN=T")
        (field (name "DB_APPROVED_BY") "ISHIDDEN=T")
      )
      (libsource (lib "Database_Libs1") (part "TEST_POINT_1"))
    )
    (comp (ref "TP132")
      (value "TEST_POINT_1")
      (footprint "SMD_TP_100-254")
      (fields
        (field (name "DB_PART_NUMBER") "TPO000000001")
        (field (name "DB_MANUFACTURER_PART") "ISHIDDEN=T")
        (field (name "DB_APPROVED_BY") "ISHIDDEN=T")
      )
      (libsource (lib "Database_Libs1") (part "TEST_POINT_1"))
    )
    (comp (ref "U6")
      (value "IC_BDXXKA5WF")
      (footprint "SMD_SOIC127P620X160-8N")
      (fields
        (field (name "DB_PART_NUMBER") "PSU000000127")
        (field (name "DB_VALUE") "BD33KA5WF-E2")
        (field (name "DB_MANUFACTURER_PART") "ROHM        BD33KA5WF-E2")
        (field (name "DB_APPROVED_BY") "VSN")
      )
      (libsource (lib "Database_Libs1") (part "IC_BDXXKA5WF"))
    )
    (comp (ref "U7")
      (value "IC_IN1OUT3GND4")
      (footprint "SMD_TO254P1542X460-3_4N")
      (fields
        (field (name "DB_PART_NUMBER") "PSU000000129")
        (field (name "DB_VALUE") "L7805CD2T-TR")
        (field (name "DB_MANUFACTURER_PART") "ST       L7805CD2T-TR")
        (field (name "DB_APPROVED_BY") "VSN")
      )
      (libsource (lib "Database_Libs1") (part "IC_IN1OUT3GND4"))
    )
    (comp (ref "U8")
      (value "IC_VIN1GND4VOUT3")
      (footprint "SMD_TO229P991X239-4N_DPAK")
      (fields
        (field (name "DB_PART_NUMBER") "PSU000000031")
        (field (name "DB_VALUE") "MC78M05BDTRKG")
        (field (name "DB_MANUFACTURER_PART") "ON Semiconductor       MC78M05BDTRKG")
        (field (name "DB_APPROVED_BY") "VSN")
      )
      (libsource (lib "Database_Libs1") (part "IC_VIN1GND4VOUT3"))
    )
    (comp (ref "U9")
      (value "IC_BD00KA5WF")
      (footprint "SMD_SOIC127P620X160-8N")
      (fields
        (field (name "DB_PART_NUMBER") "PSU000000128")
        (field (name "DB_VALUE") "BD00KA5WF-E2")
        (field (name "DB_MANUFACTURER_PART") "ROHM        BD00KA5WF-E2")
        (field (name "DB_APPROVED_BY") "VSN")
      )
      (libsource (lib "Database_Libs1") (part "IC_BD00KA5WF"))
    )
    (comp (ref "U10")
      (value "IC_DSPIC33EP256MU806-QFN64")
      (footprint "SMD_QFP50P1200X1200X120-64N")
      (fields
        (field (name "DB_PART_NUMBER") "MCU000000070")
        (field (name "DB_VALUE") "dsPIC33EP256MU806")
        (field (name "DB_MANUFACTURER_PART") "MICROCHIP        DSPIC33EP256MU806-E/PT")
        (field (name "DB_APPROVED_BY") "VSN")
      )
      (libsource (lib "Database_Libs1") (part "IC_DSPIC33EP256MU806-QFN64"))
    )
    (comp (ref "U28")
      (value "IC_LM2931AD-5.0R2G_SO-8")
      (footprint "SMD_SOIC127P600X175-8N")
      (fields
        (field (name "DB_PART_NUMBER") "PSU000000125")
        (field (name "DB_VALUE") "AP78L05SG-13")
        (field (name "DB_MANUFACTURER_PART") "DIODES        AP78L05SG-13")
        (field (name "DB_APPROVED_BY") "VSN")
      )
      (libsource (lib "Database_Libs1") (part "IC_LM2931AD-5.0R2G_SO-8"))
    )
    (comp (ref "U29")
      (value "IC_BD00KA5WF")
      (footprint "SMD_SOIC127P620X160-8N")
      (fields
        (field (name "DB_PART_NUMBER") "PSU000000128")
        (field (name "DB_VALUE") "BD00KA5WF-E2")
        (field (name "DB_MANUFACTURER_PART") "ROHM        BD00KA5WF-E2")
        (field (name "DB_APPROVED_BY") "VSN")
      )
      (libsource (lib "Database_Libs1") (part "IC_BD00KA5WF"))
    )
    (comp (ref "Y1")
      (value "XTAL")
      (footprint "SMD_HC49_XTAL1140X480X420N")
      (fields
        (field (name "DB_PART_NUMBER") "OSC000000012")
        (field (name "DB_VALUE") "4.00MHz HC49/4HSMX")
        (field (name "DB_MANUFACTURER_PART") "IQD       4.00MHz HC49/4HSMX")
        (field (name "DB_APPROVED_BY") "VSN")
      )
      (libsource (lib "Database_Libs1") (part "XTAL"))
    )
  )
  (nets
    (net (code "1") (name "/0.9V") (class "Default")
      (node (ref "C231") (pin "1") (pinfunction "1_1") (pintype "passive"))
      (node (ref "C232") (pin "1") (pinfunction "1_1") (pintype "passive"))
      (node (ref "R27") (pin "1") (pinfunction "1_1") (pintype "passive"))
      (node (ref "U29") (pin "1") (pinfunction "OUT_1") (pintype "passive"))
    )
    (net (code "2") (name "/1.8V") (class "Default")
      (node (ref "C16") (pin "1") (pinfunction "1_1") (pintype "passive"))
      (node (ref "C17") (pin "1") (pinfunction "1_1") (pintype "passive"))
      (node (ref "R16") (pin "1") (pinfunction "1_1") (pintype "passive"))
      (node (ref "U9") (pin "1") (pinfunction "OUT_1") (pintype "passive"))
    )
    (net (code "3") (name "/1V") (class "Default")
      (node (ref "R6") (pin "2") (pinfunction "2_2") (pintype "passive"))
    )
    (net (code "4") (name "/3.3V") (class "Default")
      (node (ref "C13") (pin "2") (pinfunction "2_2") (pintype "passive"))
      (node (ref "C14") (pin "1") (pinfunction "1_1") (pintype "passive"))
      (node (ref "C347") (pin "1") (pinfunction "1_1") (pintype "passive"))
      (node (ref "C6") (pin "1") (pinfunction "1_1") (pintype "passive"))
      (node (ref "C608") (pin "1") (pinfunction "1_1") (pintype "passive"))
      (node (ref "C7") (pin "1") (pinfunction "1_1") (pintype "passive"))
      (node (ref "C8") (pin "1") (pinfunction "1_1") (pintype "passive"))
      (node (ref "C9") (pin "1") (pinfunction "1_1") (pintype "passive"))
      (node (ref "J1") (pin "2") (pinfunction "2_2") (pintype "passive"))
      (node (ref "R14") (pin "2") (pinfunction "2_2") (pintype "passive"))
      (node (ref "R26") (pin "1") (pinfunction "1_1") (pintype "passive"))
      (node (ref "R31") (pin "2") (pinfunction "2_2") (pintype "passive"))
      (node (ref "U10") (pin "10") (pinfunction "VDD_10") (pintype "passive"))
      (node (ref "U10") (pin "19") (pinfunction "AVDD_19") (pintype "passive"))
      (node (ref "U10") (pin "26") (pinfunction "VDD_26") (pintype "passive"))
      (node (ref "U10") (pin "35") (pinfunction "VUSB3V3_35") (pintype "passive"))
      (node (ref "U10") (pin "38") (pinfunction "VDD_38") (pintype "passive"))
      (node (ref "U10") (pin "57") (pinfunction "VDD_57") (pintype "passive"))
      (node (ref "U6") (pin "1") (pinfunction "OUT_1") (pintype "passive"))
    )
    (net (code "5") (name "/5.0V") (class "Default")
      (node (ref "C12") (pin "1") (pinfunction "1_1") (pintype "passive"))
      (node (ref "J3") (pin "1") (pinfunction "1_1") (pintype "passive"))
      (node (ref "R34") (pin "1") (pinfunction "1_1") (pintype "passive"))
      (node (ref "U28") (pin "1") (pinfunction "OUTPUT_1") (pintype "passive"))
      (node (ref "U7") (pin "3") (pinfunction "Vout_3") (pintype "passive"))
      (node (ref "U8") (pin "3") (pinfunction "Vout_3") (pintype "passive"))
    )
    (net (code "6") (name "/12V") (class "Default")
      (node (ref "D26") (pin "1") (pinfunction "C_1") (pintype "passive"))
      (node (ref "D28") (pin "1") (pinfunction "C_1") (pintype "passive"))
      (node (ref "D30") (pin "1") (pinfunction "C_1") (pintype "passive"))
      (node (ref "D32") (pin "1") (pinfunction "C_1") (pintype "passive"))
      (node (ref "D8") (pin "2") (pinfunction "A_2") (pintype "passive"))
      (node (ref "J3") (pin "3") (pinfunction "3_3") (pintype "passive"))
      (node (ref "J4") (pin "1") (pinfunction "1_1") (pintype "passive"))
      (node (ref "J4") (pin "2") (pinfunction "2_2") (pintype "passive"))
      (node (ref "J4") (pin "3") (pinfunction "3_3") (pintype "passive"))
      (node (ref "J5") (pin "1") (pinfunction "1_1") (pintype "passive"))
      (node (ref "J5") (pin "2") (pinfunction "2_2") (pintype "passive"))
      (node (ref "J5") (pin "3") (pinfunction "3_3") (pintype "passive"))
      (node (ref "J6") (pin "1") (pinfunction "1_1") (pintype "passive"))
      (node (ref "J6") (pin "2") (pinfunction "2_2") (pintype "passive"))
      (node (ref "J6") (pin "3") (pinfunction "3_3") (pintype "passive"))
      (node (ref "J7") (pin "1") (pinfunction "1_1") (pintype "passive"))
      (node (ref "J7") (pin "2") (pinfunction "2_2") (pintype "passive"))
      (node (ref "J7") (pin "3") (pinfunction "3_3") (pintype "passive"))
      (node (ref "R13") (pin "2") (pinfunction "2_2") (pintype "passive"))
    )
    (net (code "7") (name "/D+") (class "Default")
      (node (ref "D6") (pin "1") (pinfunction "1_1") (pintype "passive"))
      (node (ref "J2") (pin "3") (pinfunction "3_3") (pintype "passive"))
      (node (ref "U10") (pin "37") (pinfunction "D+/RG2_37") (pintype "passive"))
    )
    (net (code "8") (name "/D-") (class "Default")
      (node (ref "D6") (pin "3") (pinfunction "3_3") (pintype "passive"))
      (node (ref "J2") (pin "2") (pinfunction "2_2") (pintype "passive"))
      (node (ref "U10") (pin "36") (pinfunction "D-/RG3_36") (pintype "passive"))
    )
    (net (code "9") (name "/FB") (class "Default")
      (node (ref "C3") (pin "1") (pinfunction "1_1") (pintype "passive"))
      (node (ref "R6") (pin "1") (pinfunction "1_1") (pintype "passive"))
      (node (ref "U10") (pin "17") (pinfunction "PGEC1/AN6/RPI38/RB6_17") (pintype "passive"))
    )
    (net (code "10") (name "/GREEN") (class "Default")
      (node (ref "D2") (pin "2") (pinfunction "A_2") (pintype "passive"))
      (node (ref "U10") (pin "47") (pinfunction "PGED2/SOSCI/C3IN3-/RPI61/RC13_47") (pintype "passive"))
    )
    (net (code "11") (name "/LDO3.3V-5.0V") (class "Default")
      (node (ref "C1") (pin "1") (pinfunction "1_1") (pintype "passive"))
      (node (ref "R14") (pin "1") (pinfunction "1_1") (pintype "passive"))
      (node (ref "R15") (pin "1") (pinfunction "1_1") (pintype "passive"))
      (node (ref "U29") (pin "5") (pinfunction "CTL_5") (pintype "passive"))
      (node (ref "U29") (pin "8") (pinfunction "VCC_8") (pintype "passive"))
      (node (ref "U9") (pin "5") (pinfunction "CTL_5") (pintype "passive"))
      (node (ref "U9") (pin "8") (pinfunction "VCC_8") (pintype "passive"))
    )
    (net (code "12") (name "/LDO5.0V") (class "Default")
      (node (ref "C15") (pin "1") (pinfunction "1_1") (pintype "passive"))
      (node (ref "R15") (pin "2") (pinfunction "2_2") (pintype "passive"))
      (node (ref "R33") (pin "1") (pinfunction "1_1") (pintype "passive"))
      (node (ref "R34") (pin "2") (pinfunction "2_2") (pintype "passive"))
      (node (ref "U6") (pin "5") (pinfunction "CTL_5") (pintype "passive"))
      (node (ref "U6") (pin "8") (pinfunction "VCC_8") (pintype "passive"))
    )
    (net (code "13") (name "/LM12V") (class "Default")
      (node (ref "C592") (pin "1") (pinfunction "1_1") (pintype "passive"))
      (node (ref "D8") (pin "1") (pinfunction "C_1") (pintype "passive"))
      (node (ref "R13") (pin "1") (pinfunction "1_1") (pintype "passive"))
      (node (ref "U28") (pin "8") (pinfunction "INPUT_8") (pintype "passive"))
      (node (ref "U7") (pin "1") (pinfunction "Vin_1") (pintype "passive"))
      (node (ref "U8") (pin "1") (pinfunction "Vin_1") (pintype "passive"))
    )
    (net (code "14") (name "/MCLR") (class "Default")
      (node (ref "C5") (pin "1") (pinfunction "1_1") (pintype "passive"))
      (node (ref "J1") (pin "1") (pinfunction "1_1") (pintype "passive"))
      (node (ref "R31") (pin "1") (pinfunction "1_1") (pintype "passive"))
      (node (ref "U10") (pin "7") (pinfunction "~{MCLR}_7") (pintype "passive"))
    )
    (net (code "15") (name "/MCU5.0V") (class "Default")
      (node (ref "R32") (pin "2") (pinfunction "2_2") (pintype "passive"))
      (node (ref "U10") (pin "34") (pinfunction "VBUS_34") (pintype "passive"))
    )
    (net (code "16") (name "/Main OSC In") (class "Default")
      (node (ref "C10") (pin "1") (pinfunction "1_1") (pintype "passive"))
      (node (ref "U10") (pin "39") (pinfunction "OSC1/RPI60/RC12_39") (pintype "passive"))
      (node (ref "Y1") (pin "1") (pinfunction "1_1") (pintype "passive"))
    )
    (net (code "17") (name "/Main OSC Out") (class "Default")
      (node (ref "C11") (pin "1") (pinfunction "1_1") (pintype "passive"))
      (node (ref "U10") (pin "40") (pinfunction "OSC2/CLKO/RC15_40") (pintype "passive"))
      (node (ref "Y1") (pin "2") (pinfunction "2_2") (pintype "passive"))
    )
    (net (code "18") (name "/ORANGE") (class "Default")
      (node (ref "D4") (pin "2") (pinfunction "A_2") (pintype "passive"))
      (node (ref "U10") (pin "45") (pinfunction "PMCS1/RPI75/RD11_45") (pintype "passive"))
    )
    (net (code "19") (name "/PGC") (class "Default")
      (node (ref "J1") (pin "5") (pinfunction "5_5") (pintype "passive"))
      (node (ref "U10") (pin "15") (pinfunction "PGEC3/AN1/VREF-/RPI33/RB1_15") (pintype "passive"))
    )
    (net (code "20") (name "/PGD") (class "Default")
      (node (ref "J1") (pin "4") (pinfunction "4_4") (pintype "passive"))
      (node (ref "U10") (pin "16") (pinfunction "PGED3/AN0/VREF+/RPI32/RB0_16") (pintype "passive"))
    )
    (net (code "21") (name "/PWM1H") (class "Default")
      (node (ref "U10") (pin "61") (pinfunction "AN25/PWM1H/PMD1/RPI81/RE1_61") (pintype "passive"))
    )
    (net (code "22") (name "/PWM1L") (class "Default")
      (node (ref "U10") (pin "60") (pinfunction "AN24/PWM1L/PMD0/RP80/RE0_60") (pintype "passive"))
    )
    (net (code "23") (name "/PWM2H") (class "Default")
      (node (ref "U10") (pin "63") (pinfunction "AN27/PWM2H/PMD3/RPI83/RE3_63") (pintype "passive"))
    )
    (net (code "24") (name "/PWM2L") (class "Default")
      (node (ref "U10") (pin "62") (pinfunction "AN26/PWM2L/PMD2/RP82/RE2_62") (pintype "passive"))
    )
    (net (code "25") (name "/PWM3H") (class "Default")
      (node (ref "U10") (pin "1") (pinfunction "AN29/PWM3H/PMD5/RP85/RE5_1") (pintype "passive"))
    )
    (net (code "26") (name "/PWM3L") (class "Default")
      (node (ref "U10") (pin "64") (pinfunction "AN28/PWM3L/PMD4/RP84/RE4_64") (pintype "passive"))
    )
    (net (code "27") (name "/PWM4H") (class "Default")
      (node (ref "U10") (pin "3") (pinfunction "AN31/PWM4H/PMD7/RP87/RE7_3") (pintype "passive"))
    )
    (net (code "28") (name "/PWM4L") (class "Default")
      (node (ref "U10") (pin "2") (pinfunction "AN30/PWM4L/PMD6/RPI86/RE6_2") (pintype "passive"))
    )
    (net (code "29") (name "/RED") (class "Default")
      (node (ref "D1") (pin "2") (pinfunction "A_2") (pintype "passive"))
      (node (ref "U10") (pin "48") (pinfunction "PGEC2/SOSCO/C3IN1-/T1CK/RPI62/RC14_48") (pintype "passive"))
    )
    (net (code "30") (name "/RESET_ASIC") (class "Default")
      (node (ref "R26") (pin "2") (pinfunction "2_2") (pintype "passive"))
      (node (ref "U10") (pin "43") (pinfunction "ASDA1/DPLN/RPI73/RD9_43") (pintype "passive"))
    )
    (net (code "31") (name "/SPI_CS") (class "Default")
      (node (ref "U10") (pin "8") (pinfunction "C2IN1-/PMA2/RPI121/RG9_8") (pintype "passive"))
    )
    (net (code "32") (name "/SPI_MISO") (class "Default")
      (node (ref "U10") (pin "5") (pinfunction "C1IN1-/SDI2/PMA4/RPI119/RG7_5") (pintype "passive"))
    )
    (net (code "33") (name "/SPI_MOSI") (class "Default")
      (node (ref "U10") (pin "6") (pinfunction "C2IN3-/SDO2/PMA3/RP120/RG8_6") (pintype "passive"))
    )
    (net (code "34") (name "/SPI_SCK") (class "Default")
      (node (ref "U10") (pin "4") (pinfunction "C1IN3-/SCK2/PMA5/RP118/RG6_4") (pintype "passive"))
    )
    (net (code "35") (name "/USB5.0V") (class "Default")
      (node (ref "D6") (pin "4") (pinfunction "4_4") (pintype "passive"))
      (node (ref "D6") (pin "6") (pinfunction "6_6") (pintype "passive"))
      (node (ref "J2") (pin "1") (pinfunction "1_1") (pintype "passive"))
      (node (ref "R32") (pin "1") (pinfunction "1_1") (pintype "passive"))
      (node (ref "R33") (pin "2") (pinfunction "2_2") (pintype "passive"))
    )
    (net (code "36") (name "/VCAP") (class "Default")
      (node (ref "C2") (pin "1") (pinfunction "1_1") (pintype "passive"))
      (node (ref "U10") (pin "56") (pinfunction "VCAP_56") (pintype "passive"))
    )
    (net (code "37") (name "/YELLOW") (class "Default")
      (node (ref "D3") (pin "2") (pinfunction "A_2") (pintype "passive"))
      (node (ref "U10") (pin "44") (pinfunction "ASCL1/PMCS2/RPI74/RD10_44") (pintype "passive"))
    )
    (net (code "38") (name "GND") (class "Default")
      (node (ref "C1") (pin "2") (pinfunction "2_2") (pintype "passive"))
      (node (ref "C10") (pin "2") (pinfunction "2_2") (pintype "passive"))
      (node (ref "C11") (pin "2") (pinfunction "2_2") (pintype "passive"))
      (node (ref "C12") (pin "2") (pinfunction "2_2") (pintype "passive"))
      (node (ref "C13") (pin "1") (pinfunction "1_1") (pintype "passive"))
      (node (ref "C14") (pin "2") (pinfunction "2_2") (pintype "passive"))
      (node (ref "C15") (pin "2") (pinfunction "2_2") (pintype "passive"))
      (node (ref "C16") (pin "2") (pinfunction "2_2") (pintype "passive"))
      (node (ref "C17") (pin "2") (pinfunction "2_2") (pintype "passive"))
      (node (ref "C2") (pin "2") (pinfunction "2_2") (pintype "passive"))
      (node (ref "C231") (pin "2") (pinfunction "2_2") (pintype "passive"))
      (node (ref "C232") (pin "2") (pinfunction "2_2") (pintype "passive"))
      (node (ref "C3") (pin "2") (pinfunction "2_2") (pintype "passive"))
      (node (ref "C347") (pin "2") (pinfunction "2_2") (pintype "passive"))
      (node (ref "C5") (pin "2") (pinfunction "2_2") (pintype "passive"))
      (node (ref "C592") (pin "2") (pinfunction "2_2") (pintype "passive"))
      (node (ref "C6") (pin "2") (pinfunction "2_2") (pintype "passive"))
      (node (ref "C608") (pin "2") (pinfunction "2_2") (pintype "passive"))
      (node (ref "C7") (pin "2") (pinfunction "2_2") (pintype "passive"))
      (node (ref "C8") (pin "2") (pinfunction "2_2") (pintype "passive"))
      (node (ref "C9") (pin "2") (pinfunction "2_2") (pintype "passive"))
      (node (ref "D1") (pin "1") (pinfunction "C_1") (pintype "passive"))
      (node (ref "D2") (pin "1") (pinfunction "C_1") (pintype "passive"))
      (node (ref "D26") (pin "2") (pinfunction "A_2") (pintype "passive"))
      (node (ref "D28") (pin "2") (pinfunction "A_2") (pintype "passive"))
      (node (ref "D3") (pin "1") (pinfunction "C_1") (pintype "passive"))
      (node (ref "D30") (pin "2") (pinfunction "A_2") (pintype "passive"))
      (node (ref "D32") (pin "2") (pinfunction "A_2") (pintype "passive"))
      (node (ref "D4") (pin "1") (pinfunction "C_1") (pintype "passive"))
      (node (ref "D6") (pin "2") (pinfunction "2_2") (pintype "passive"))
      (node (ref "D6") (pin "5") (pinfunction "5_5") (pintype "passive"))
      (node (ref "J1") (pin "3") (pinfunction "3_3") (pintype "passive"))
      (node (ref "J13") (pin "1") (pinfunction "1_1") (pintype "passive"))
      (node (ref "J14") (pin "1") (pinfunction "1_1") (pintype "passive"))
      (node (ref "J15") (pin "1") (pinfunction "1_1") (pintype "passive"))
      (node (ref "J16") (pin "1") (pinfunction "1_1") (pintype "passive"))
      (node (ref "J17") (pin "1") (pinfunction "1_1") (pintype "passive"))
      (node (ref "J18") (pin "1") (pinfunction "1_1") (pintype "passive"))
      (node (ref "J19") (pin "1") (pinfunction "1_1") (pintype "passive"))
      (node (ref "J2") (pin "5") (pinfunction "5_5") (pintype "passive"))
      (node (ref "J2") (pin "6") (pinfunction "6_6") (pintype "passive"))
      (node (ref "J2") (pin "7") (pinfunction "7_7") (pintype "passive"))
      (node (ref "J2") (pin "8") (pinfunction "8_8") (pintype "passive"))
      (node (ref "J2") (pin "9") (pinfunction "9_9") (pintype "passive"))
      (node (ref "J20") (pin "1") (pinfunction "1_1") (pintype "passive"))
      (node (ref "J21") (pin "1") (pinfunction "1_1") (pintype "passive"))
      (node (ref "J22") (pin "1") (pinfunction "1_1") (pintype "passive"))
      (node (ref "J23") (pin "1") (pinfunction "1_1") (pintype "passive"))
      (node (ref "J24") (pin "1") (pinfunction "1_1") (pintype "passive"))
      (node (ref "J3") (pin "2") (pinfunction "2_2") (pintype "passive"))
      (node (ref "J4") (pin "4") (pinfunction "4_4") (pintype "passive"))
      (node (ref "J4") (pin "5") (pinfunction "5_5") (pintype "passive"))
      (node (ref "J4") (pin "6") (pinfunction "6_6") (pintype "passive"))
      (node (ref "J5") (pin "4") (pinfunction "4_4") (pintype "passive"))
      (node (ref "J5") (pin "5") (pinfunction "5_5") (pintype "passive"))
      (node (ref "J5") (pin "6") (pinfunction "6_6") (pintype "passive"))
      (node (ref "J6") (pin "4") (pinfunction "4_4") (pintype "passive"))
      (node (ref "J6") (pin "5") (pinfunction "5_5") (pintype "passive"))
      (node (ref "J6") (pin "6") (pinfunction "6_6") (pintype "passive"))
      (node (ref "J7") (pin "4") (pinfunction "4_4") (pintype "passive"))
      (node (ref "J7") (pin "5") (pinfunction "5_5") (pintype "passive"))
      (node (ref "J7") (pin "6") (pinfunction "6_6") (pintype "passive"))
      (node (ref "J9") (pin "1") (pinfunction "1_1") (pintype "passive"))
      (node (ref "R17") (pin "2") (pinfunction "2_2") (pintype "passive"))
      (node (ref "R28") (pin "2") (pinfunction "2_2") (pintype "passive"))
      (node (ref "U10") (pin "20") (pinfunction "AVSS_20") (pintype "passive"))
      (node (ref "U10") (pin "25") (pinfunction "VSS_25") (pintype "passive"))
      (node (ref "U10") (pin "41") (pinfunction "VSS_41") (pintype "passive"))
      (node (ref "U10") (pin "9") (pinfunction "VSS_9") (pintype "passive"))
      (node (ref "U28") (pin "2") (pinfunction "GND_2") (pintype "passive"))
      (node (ref "U28") (pin "3") (pinfunction "GND_3") (pintype "passive"))
      (node (ref "U28") (pin "4") (pinfunction "N.C._4") (pintype "passive"))
      (node (ref "U28") (pin "5") (pinfunction "N.C._5") (pintype "passive"))
      (node (ref "U28") (pin "6") (pinfunction "GND_6") (pintype "passive"))
      (node (ref "U28") (pin "7") (pinfunction "GND_7") (pintype "passive"))
      (node (ref "U29") (pin "6") (pinfunction "GND_6") (pintype "passive"))
      (node (ref "U29") (pin "7") (pinfunction "GND_7") (pintype "passive"))
      (node (ref "U6") (pin "6") (pinfunction "GND_6") (pintype "passive"))
      (node (ref "U6") (pin "7") (pinfunction "GND_7") (pintype "passive"))
      (node (ref "U7") (pin "4") (pinfunction "GND_4") (pintype "passive"))
      (node (ref "U8") (pin "4") (pinfunction "GND_4") (pintype "passive"))
      (node (ref "U9") (pin "6") (pinfunction "GND_6") (pintype "passive"))
      (node (ref "U9") (pin "7") (pinfunction "GND_7") (pintype "passive"))
    )
    (net (code "39") (name "Net-(U9-ADJ)") (class "Default")
      (node (ref "R16") (pin "2") (pinfunction "2_2") (pintype "passive"))
      (node (ref "R17") (pin "1") (pinfunction "1_1") (pintype "passive"))
      (node (ref "U9") (pin "2") (pinfunction "ADJ_2") (pintype "passive"))
    )
    (net (code "40") (name "Net-(U10-AN2{slash}C2IN2-{slash}VMIO{slash}RPI34{slash}RB2)") (class "Default")
      (node (ref "TP7") (pin "1") (pinfunction "1_1") (pintype "passive"))
      (node (ref "U10") (pin "14") (pinfunction "AN2/C2IN2-/VMIO/RPI34/RB2_14") (pintype "passive"))
    )
    (net (code "41") (name "Net-(U10-AN3{slash}C2IN1+{slash}VPIO{slash}RPI35{slash}RB3)") (class "Default")
      (node (ref "TP6") (pin "1") (pinfunction "1_1") (pintype "passive"))
      (node (ref "U10") (pin "13") (pinfunction "AN3/C2IN1+/VPIO/RPI35/RB3_13") (pintype "passive"))
    )
    (net (code "42") (name "Net-(U10-AN4{slash}C1IN2-{slash}USBOEN{slash}RPI36{slash}RB4)") (class "Default")
      (node (ref "TP5") (pin "1") (pinfunction "1_1") (pintype "passive"))
      (node (ref "U10") (pin "12") (pinfunction "AN4/C1IN2-/USBOEN/RPI36/RB4_12") (pintype "passive"))
    )
    (net (code "43") (name "Net-(U10-AN5{slash}C1IN1+{slash}VBUSON{slash}VBUSST{slash}RPI37{slash}RB5)") (class "Default")
      (node (ref "TP128") (pin "1") (pinfunction "1_1") (pintype "passive"))
      (node (ref "U10") (pin "11") (pinfunction "AN5/C1IN1+/VBUSON/VBUSST/RPI37/RB5_11") (pintype "passive"))
    )
    (net (code "44") (name "Net-(U10-AN8{slash}PMA6{slash}RPI40{slash}RB8)") (class "Default")
      (node (ref "TP10") (pin "1") (pinfunction "1_1") (pintype "passive"))
      (node (ref "U10") (pin "21") (pinfunction "AN8/PMA6/RPI40/RB8_21") (pintype "passive"))
    )
    (net (code "45") (name "Net-(U10-AN9{slash}PMA7{slash}{slash}RPI41{slash}RB9)") (class "Default")
      (node (ref "TP11") (pin "1") (pinfunction "1_1") (pintype "passive"))
      (node (ref "U10") (pin "22") (pinfunction "AN9/PMA7//RPI41/RB9_22") (pintype "passive"))
    )
    (net (code "46") (name "Net-(U10-AN14{slash}PMA1{slash}RPI46{slash}RB14)") (class "Default")
      (node (ref "TP124") (pin "1") (pinfunction "1_1") (pintype "passive"))
      (node (ref "U10") (pin "29") (pinfunction "AN14/PMA1/RPI46/RB14_29") (pintype "passive"))
    )
    (net (code "47") (name "Net-(U10-AN15{slash}PMA0{slash}RPI47{slash}RB15)") (class "Default")
      (node (ref "TP125") (pin "1") (pinfunction "1_1") (pintype "passive"))
      (node (ref "U10") (pin "30") (pinfunction "AN15/PMA0/RPI47/RB15_30") (pintype "passive"))
    )
    (net (code "48") (name "Net-(U10-C3IN1+{slash}VCMPST3{slash}RP71{slash}RD7)") (class "Default")
      (node (ref "TP18") (pin "1") (pinfunction "1_1") (pintype "passive"))
      (node (ref "U10") (pin "55") (pinfunction "C3IN1+/VCMPST3/RP71/RD7_55") (pintype "passive"))
    )
    (net (code "49") (name "Net-(U10-C3IN2-{slash}RP70{slash}RD6)") (class "Default")
      (node (ref "TP19") (pin "1") (pinfunction "1_1") (pintype "passive"))
      (node (ref "U10") (pin "54") (pinfunction "C3IN2-/RP70/RD6_54") (pintype "passive"))
    )
    (net (code "50") (name "Net-(U10-DPH{slash}RP66{slash}RD2)") (class "Default")
      (node (ref "TP22") (pin "1") (pinfunction "1_1") (pintype "passive"))
      (node (ref "U10") (pin "50") (pinfunction "DPH/RP66/RD2_50") (pintype "passive"))
    )
    (net (code "51") (name "Net-(U10-INT0{slash}DMH{slash}RP64{slash}RD0)") (class "Default")
      (node (ref "TP24") (pin "1") (pinfunction "1_1") (pintype "passive"))
      (node (ref "U10") (pin "46") (pinfunction "INT0/DMH/RP64/RD0_46") (pintype "passive"))
    )
    (net (code "52") (name "Net-(U10-PGED1{slash}AN7{slash}RCV{slash}RPI39{slash}RB7)") (class "Default")
      (node (ref "TP26") (pin "1") (pinfunction "1_1") (pintype "passive"))
      (node (ref "U10") (pin "18") (pinfunction "PGED1/AN7/RCV/RPI39/RB7_18") (pintype "passive"))
    )
    (net (code "53") (name "Net-(U10-PMBE{slash}RP67{slash}RD3)") (class "Default")
      (node (ref "TP17") (pin "1") (pinfunction "1_1") (pintype "passive"))
      (node (ref "U10") (pin "51") (pinfunction "PMBE/RP67/RD3_51") (pintype "passive"))
    )
    (net (code "54") (name "Net-(U10-PMRD{slash}RP69{slash}RD5)") (class "Default")
      (node (ref "TP25") (pin "1") (pinfunction "1_1") (pintype "passive"))
      (node (ref "U10") (pin "53") (pinfunction "PMRD/RP69/RD5_53") (pintype "passive"))
    )
    (net (code "55") (name "Net-(U10-PMWR{slash}RP68{slash}RD4)") (class "Default")
      (node (ref "TP20") (pin "1") (pinfunction "1_1") (pintype "passive"))
      (node (ref "U10") (pin "52") (pinfunction "PMWR/RP68/RD4_52") (pintype "passive"))
    )
    (net (code "56") (name "Net-(U10-RTCC{slash}DMLN{slash}RPI72{slash}RD8)") (class "Default")
      (node (ref "TP13") (pin "1") (pinfunction "1_1") (pintype "passive"))
      (node (ref "U10") (pin "42") (pinfunction "RTCC/DMLN/RPI72/RD8_42") (pintype "passive"))
    )
    (net (code "57") (name "Net-(U10-SCL2{slash}PMA8{slash}RP101{slash}RF5)") (class "Default")
      (node (ref "TP127") (pin "1") (pinfunction "1_1") (pintype "passive"))
      (node (ref "U10") (pin "32") (pinfunction "SCL2/PMA8/RP101/RF5_32") (pintype "passive"))
    )
    (net (code "58") (name "Net-(U10-SDA2{slash}PMA9{slash}RP100{slash}RF4)") (class "Default")
      (node (ref "TP126") (pin "1") (pinfunction "1_1") (pintype "passive"))
      (node (ref "U10") (pin "31") (pinfunction "SDA2/PMA9/RP100/RF4_31") (pintype "passive"))
    )
    (net (code "59") (name "Net-(U10-TCK{slash}AN12{slash}PMA11{slash}RPI44{slash}RB12)") (class "Default")
      (node (ref "TP2") (pin "1") (pinfunction "1_1") (pintype "passive"))
      (node (ref "U10") (pin "27") (pinfunction "TCK/AN12/PMA11/RPI44/RB12_27") (pintype "passive"))
    )
    (net (code "60") (name "Net-(U10-TDI{slash}AN13{slash}PMA10{slash}RPI45{slash}RB13)") (class "Default")
      (node (ref "TP123") (pin "1") (pinfunction "1_1") (pintype "passive"))
      (node (ref "U10") (pin "28") (pinfunction "TDI/AN13/PMA10/RPI45/RB13_28") (pintype "passive"))
    )
    (net (code "61") (name "Net-(U10-TDO{slash}AN11{slash}PMA12{slash}RPI43{slash}RB11)") (class "Default")
      (node (ref "TP132") (pin "1") (pinfunction "1_1") (pintype "passive"))
      (node (ref "U10") (pin "24") (pinfunction "TDO/AN11/PMA12/RPI43/RB11_24") (pintype "passive"))
    )
    (net (code "62") (name "Net-(U10-TMS{slash}AN10{slash}CVREF{slash}PMA13{slash}RPI42{slash}RB10)") (class "Default")
      (node (ref "TP131") (pin "1") (pinfunction "1_1") (pintype "passive"))
      (node (ref "U10") (pin "23") (pinfunction "TMS/AN10/CVREF/PMA13/RPI42/RB10_23") (pintype "passive"))
    )
    (net (code "63") (name "Net-(U10-USBID{slash}RP99{slash}RF3)") (class "Default")
      (node (ref "TP21") (pin "1") (pinfunction "1_1") (pintype "passive"))
      (node (ref "U10") (pin "33") (pinfunction "USBID/RP99/RF3_33") (pintype "passive"))
    )
    (net (code "64") (name "Net-(U10-VCMPST1{slash}RP96{slash}RF0)") (class "Default")
      (node (ref "TP12") (pin "1") (pinfunction "1_1") (pintype "passive"))
      (node (ref "U10") (pin "58") (pinfunction "VCMPST1/RP96/RF0_58") (pintype "passive"))
    )
    (net (code "65") (name "Net-(U10-VCMPST2{slash}RP97{slash}RF1)") (class "Default")
      (node (ref "TP129") (pin "1") (pinfunction "1_1") (pintype "passive"))
      (node (ref "U10") (pin "59") (pinfunction "VCMPST2/RP97/RF1_59") (pintype "passive"))
    )
    (net (code "66") (name "Net-(U10-VCPCON{slash}RP65{slash}RD1)") (class "Default")
      (node (ref "TP23") (pin "1") (pinfunction "1_1") (pintype "passive"))
      (node (ref "U10") (pin "49") (pinfunction "VCPCON/RP65/RD1_49") (pintype "passive"))
    )
    (net (code "67") (name "Net-(U29-ADJ)") (class "Default")
      (node (ref "R27") (pin "2") (pinfunction "2_2") (pintype "passive"))
      (node (ref "R28") (pin "1") (pinfunction "1_1") (pintype "passive"))
      (node (ref "U29") (pin "2") (pinfunction "ADJ_2") (pintype "passive"))
    )
    (net (code "68") (name "unconnected-(J2-Pad4)") (class "Default")
      (node (ref "J2") (pin "4") (pinfunction "4_4") (pintype "passive+no_connect"))
    )
    (net (code "69") (name "unconnected-(U6-NC-Pad2)") (class "Default")
      (node (ref "U6") (pin "2") (pinfunction "NC_2") (pintype "passive+no_connect"))
    )
    (net (code "70") (name "unconnected-(U6-NC-Pad3)") (class "Default")
      (node (ref "U6") (pin "3") (pinfunction "NC_3") (pintype "passive+no_connect"))
    )
    (net (code "71") (name "unconnected-(U6-NC-Pad4)") (class "Default")
      (node (ref "U6") (pin "4") (pinfunction "NC_4") (pintype "passive+no_connect"))
    )
    (net (code "72") (name "unconnected-(U9-NC-Pad3)") (class "Default")
      (node (ref "U9") (pin "3") (pinfunction "NC_3") (pintype "passive+no_connect"))
    )
    (net (code "73") (name "unconnected-(U9-NC-Pad4)") (class "Default")
      (node (ref "U9") (pin "4") (pinfunction "NC_4") (pintype "passive+no_connect"))
    )
    (net (code "74") (name "unconnected-(U29-NC-Pad3)") (class "Default")
      (node (ref "U29") (pin "3") (pinfunction "NC_3") (pintype "passive+no_connect"))
    )
    (net (code "75") (name "unconnected-(U29-NC-Pad4)") (class "Default")
      (node (ref "U29") (pin "4") (pinfunction "NC_4") (pintype "passive+no_connect"))
    )
  )
)
